# 13-Power-P3V3.net
KiCad netlist of a schematic drawn in Altium Designer
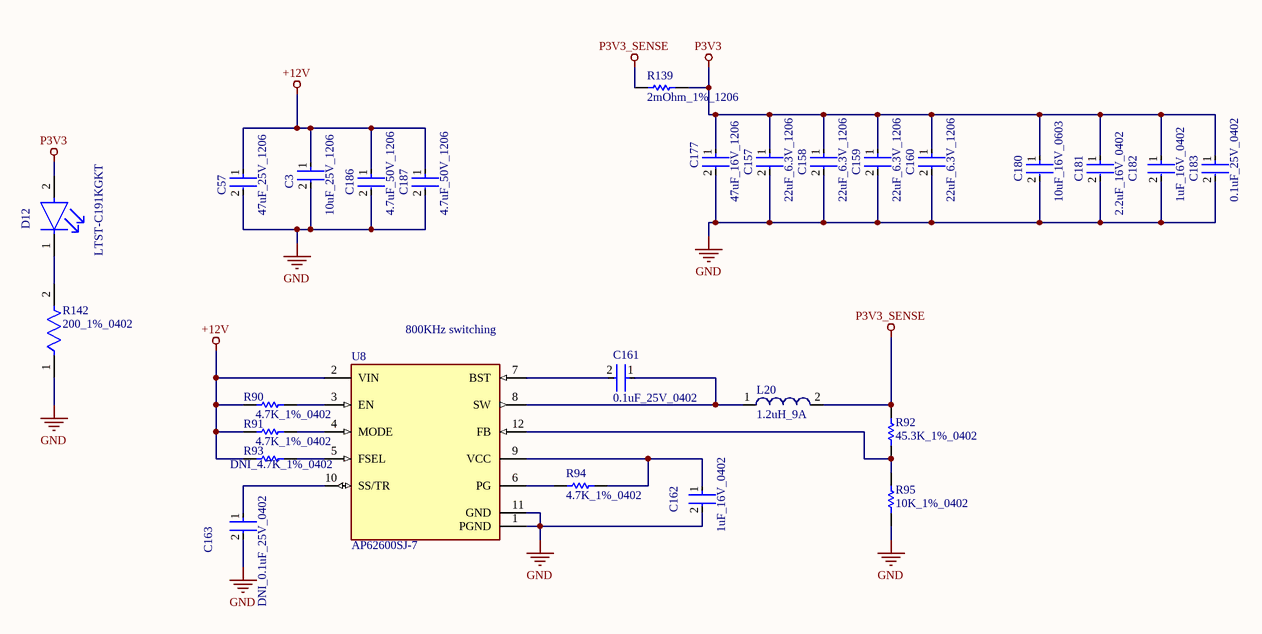
[diagram p0: 13-Power-P3V3.SchDoc]

(export (version "E")
  (design (tool "Eeschema 10.0.6"))
  (components
    (comp (ref "C3")
      (value "10uF_25V_1206")
      (footprint "FP-1206-L_3_2_0_2-W_1_6_0-IPC_A")
      (description "General Purpose Ceramic Capacitor, 1206, 10uF, 20%, X5R, 15%, 25V")
      (fields (field (name "TOLERANCE") "20%"))
      (libsource (lib "Altium Content Vault") (part "02cd4be3c70576c341d710602a673aa"))
    )
    (comp (ref "C57")
      (value "47uF_25V_1206")
      (footprint "FP-C3216-160-0_2-MFG")
      (description "Multilayer Ceramic Capacitors 47uF ±20% 25V X5R SMD 1206")
      (fields (field (name "VOLTAGE") "25V") (field (name "TOLERANCE") "20%"))
      (libsource (lib "Altium Content Vault") (part "11868f565c42a9108669ba33697ecf6"))
    )
    (comp (ref "C157")
      (value "22uF_6.3V_1206")
      (footprint "FP-1206-L_3_2_0_2-W_1_6_0-IPC_C")
      (description "General Purpose Ceramic Capacitor, 1206, 22uF, 20%, X5R, 15%, 6.3V")
      (fields (field (name "TOLERANCE") "20%") (field (name "VOLTAGE") "6.3V"))
      (libsource (lib "Altium Content Vault") (part "02cd4be3c70576c341d710602a673aa"))
    )
    (comp (ref "C158")
      (value "22uF_6.3V_1206")
      (footprint "FP-1206-L_3_2_0_2-W_1_6_0-IPC_C")
      (description "General Purpose Ceramic Capacitor, 1206, 22uF, 20%, X5R, 15%, 6.3V")
      (fields (field (name "TOLERANCE") "20%") (field (name "VOLTAGE") "6.3V"))
      (libsource (lib "Altium Content Vault") (part "02cd4be3c70576c341d710602a673aa"))
    )
    (comp (ref "C159")
      (value "22uF_6.3V_1206")
      (footprint "FP-1206-L_3_2_0_2-W_1_6_0-IPC_C")
      (description "General Purpose Ceramic Capacitor, 1206, 22uF, 20%, X5R, 15%, 6.3V")
      (fields (field (name "TOLERANCE") "20%") (field (name "VOLTAGE") "6.3V"))
      (libsource (lib "Altium Content Vault") (part "02cd4be3c70576c341d710602a673aa"))
    )
    (comp (ref "C160")
      (value "22uF_6.3V_1206")
      (footprint "FP-1206-L_3_2_0_2-W_1_6_0-IPC_C")
      (description "General Purpose Ceramic Capacitor, 1206, 22uF, 20%, X5R, 15%, 6.3V")
      (fields (field (name "TOLERANCE") "20%") (field (name "VOLTAGE") "6.3V"))
      (libsource (lib "Altium Content Vault") (part "02cd4be3c70576c341d710602a673aa"))
    )
    (comp (ref "C161")
      (value "0.1uF_25V_0402")
      (footprint "FP-0402-L_1_0_1-W_0_5_0_1-IPC_C")
      (description "General Purpose Ceramic Capacitor, 0402, 100nF, 10%, X7R, 15%, 25V")
      (fields (field (name "VOLTAGE") "25V") (field (name "TOLERANCE") "10%"))
      (libsource (lib "Altium Content Vault") (part "b4654b650e69147ec39a6b967a45e02"))
    )
    (comp (ref "C162")
      (value "1uF_16V_0402")
      (footprint "FP-0402-L_1_0_0_05-W_0_5-IPC_A")
      (description "None")
      (fields (field (name "TOLERANCE") "10%"))
      (libsource (lib "Altium Content Vault") (part "b4654b650e69147ec39a6b967a45e02"))
    )
    (comp (ref "C163")
      (value "DNI_0.1uF_25V_0402")
      (footprint "FP-0402-L_1_0_1-W_0_5_0_1-IPC_C")
      (description "General Purpose Ceramic Capacitor, 0402, 100nF, 10%, X7R, 15%, 25V")
      (fields (field (name "VOLTAGE") "25V") (field (name "TOLERANCE") "10%"))
      (libsource (lib "Altium Content Vault") (part "b4654b650e69147ec39a6b967a45e02"))
    )
    (comp (ref "C177")
      (value "47uF_16V_1206")
      (footprint "FP-C3216-160-0_2-MFG")
      (description "Multilayer Ceramic Capacitors 47uF ±20% 16V X5R SMD 1206")
      (fields (field (name "TOLERANCE") "20%"))
      (libsource (lib "Altium Content Vault") (part "11868f565c42a9108669ba33697ecf6"))
    )
    (comp (ref "C180")
      (value "10uF_16V_0603")
      (footprint "FP-0603-L_1_6_0_2-W_0_8_0-MFG")
      (description "Multilayer Ceramic Capacitor 10uF 16V X5R 20% SMD 0603 T/R")
      (fields (field (name "TOLERANCE") "20%"))
      (libsource (lib "Altium Content Vault") (part "b4654b650e69147ec39a6b967a45e02"))
    )
    (comp (ref "C181")
      (value "2.2uF_16V_0402")
      (footprint "FP-C1005-050-0_05-IPC_A")
      (description "Multilayer Ceramic Capacitors 2.2μF ±10% 16V X5R SMD 0402")
      (fields (field (name "TOLERANCE") "10%"))
      (libsource (lib "Altium Content Vault") (part "b4654b650e69147ec39a6b967a45e02"))
    )
    (comp (ref "C182")
      (value "1uF_16V_0402")
      (footprint "FP-0402-L_1_0_0_05-W_0_5-IPC_A")
      (description "None")
      (fields (field (name "TOLERANCE") "10%"))
      (libsource (lib "Altium Content Vault") (part "b4654b650e69147ec39a6b967a45e02"))
    )
    (comp (ref "C183")
      (value "0.1uF_25V_0402")
      (footprint "FP-0402-L_1_0_1-W_0_5_0_1-IPC_C")
      (description "General Purpose Ceramic Capacitor, 0402, 100nF, 10%, X7R, 15%, 25V")
      (fields (field (name "VOLTAGE") "25V") (field (name "TOLERANCE") "10%"))
      (libsource (lib "Altium Content Vault") (part "b4654b650e69147ec39a6b967a45e02"))
    )
    (comp (ref "C186")
      (value "4.7uF_50V_1206")
      (footprint "FP-GRM31C-0_2-e0_3_0_8-IPC_C")
      (description "Chip Multilayer Ceramic Capacitors for General Purpose, 1206, 4.7uF, X7R, 15%, 10%, 50V")
      (fields (field (name "VOLTAGE") "50V") (field (name "TOLERANCE") "10%"))
      (libsource (lib "Altium Content Vault") (part "02cd4be3c70576c341d710602a673aa"))
    )
    (comp (ref "C187")
      (value "4.7uF_50V_1206")
      (footprint "FP-GRM31C-0_2-e0_3_0_8-IPC_C")
      (description "Chip Multilayer Ceramic Capacitors for General Purpose, 1206, 4.7uF, X7R, 15%, 10%, 50V")
      (fields (field (name "VOLTAGE") "50V") (field (name "TOLERANCE") "10%"))
      (libsource (lib "Altium Content Vault") (part "02cd4be3c70576c341d710602a673aa"))
    )
    (comp (ref "D12")
      (value "LTST-C191KGKT")
      (footprint "FP-LTST-C191KGKT-MFG")
      (description "LED GREEN CLEAR SMD")
      (libsource (lib "Altium Content Vault") (part "8706943c75ba83719d021d2fdc84c58"))
    )
    (comp (ref "L20")
      (value "1.2uH_9A")
      (footprint "WE-LHMI 7050")
      (description "SMD Power Inductor WE-LHMI, L=1.2 µH")
      (fields (field (name "MANUFACTURER") "Wuerth Elektronik") (field (name "PARTNUMBER") "74437349012"))
      (libsource (lib "Altium Content Vault") (part "WE-IND-INDUCTOR-2"))
    )
    (comp (ref "R90")
      (value "4.7K_1%_0402")
      (footprint "RESC1005X40X25NL10T10")
      (fields (field (name "MANUFACTURER") "Bourns") (field (name "PART NUMBER") "CR0402-FX-4701GLF"))
      (libsource (lib "Altium Content Vault") (part "RES"))
    )
    (comp (ref "R91")
      (value "4.7K_1%_0402")
      (footprint "RESC1005X40X25NL10T10")
      (fields (field (name "MANUFACTURER") "Bourns") (field (name "PART NUMBER") "CR0402-FX-4701GLF"))
      (libsource (lib "Altium Content Vault") (part "RES"))
    )
    (comp (ref "R92")
      (value "45.3K_1%_0402")
      (footprint "RESC1005X40X25ML05T10")
      (fields (field (name "PART NUMBER") "RC0402FR-0745K3L") (field (name "MANUFACTURER") "Yageo / Phycomp"))
      (libsource (lib "Altium Content Vault") (part "RES"))
    )
    (comp (ref "R93")
      (value "DNI_4.7K_1%_0402")
      (footprint "RESC1005X40X25NL10T10")
      (fields (field (name "MANUFACTURER") "Bourns") (field (name "PART NUMBER") "CR0402-FX-4701GLF"))
      (libsource (lib "Altium Content Vault") (part "RES"))
    )
    (comp (ref "R94")
      (value "4.7K_1%_0402")
      (footprint "RESC1005X40X25NL10T10")
      (fields (field (name "MANUFACTURER") "Bourns") (field (name "PART NUMBER") "CR0402-FX-4701GLF"))
      (libsource (lib "Altium Content Vault") (part "RES"))
    )
    (comp (ref "R95")
      (value "10K_1%_0402")
      (footprint "RESC1005X40X25NL10T10")
      (fields (field (name "MANUFACTURER") "Bourns") (field (name "PART NUMBER") "CR0402-FX-1002GLF"))
      (libsource (lib "Altium Content Vault") (part "RES"))
    )
    (comp (ref "R139")
      (value "2mOhm_1%_1206")
      (footprint "RESC3216X89X64NL25T25")
      (fields (field (name "MANUFACTURER") "Vishay Dale") (field (name "PART NUMBER") "WSL12062L000FEA18"))
      (libsource (lib "Altium Content Vault") (part "RES"))
    )
    (comp (ref "R142")
      (value "200_1%_0402")
      (footprint "FP-ERJ2RK-IPC_A")
      (description "RES SMD 200 OHM 1% 1/10W 0402")
      (fields (field (name "TOLERANCE") "1%"))
      (libsource (lib "Altium Content Vault") (part "1029c3af85768c4190bb7ad29bc67b5"))
    )
    (comp (ref "U8")
      (value "AP62600SJ-7")
      (footprint "FP-V-QFN2030-12_Type_A-MFG")
      (description "DCDC CONV HV BUCK,V-QFN2030-12")
      (libsource (lib "Altium Content Vault") (part "03c86ce2703f4b33b3045e94f7be521"))
    )
  )
  (nets
    (net (code "1") (name "+12V") (class "Default")
      (node (ref "C186") (pin "1") (pinfunction "1_1") (pintype "passive"))
      (node (ref "C187") (pin "1") (pinfunction "1_1") (pintype "passive"))
      (node (ref "C3") (pin "1") (pinfunction "1_1") (pintype "passive"))
      (node (ref "C57") (pin "1") (pinfunction "1_1") (pintype "passive"))
      (node (ref "R90") (pin "1") (pinfunction "1_1") (pintype "passive"))
      (node (ref "R91") (pin "1") (pinfunction "1_1") (pintype "passive"))
      (node (ref "R93") (pin "1") (pinfunction "1_1") (pintype "passive"))
      (node (ref "U8") (pin "2") (pinfunction "VIN_2") (pintype "power_in"))
    )
    (net (code "2") (name "GND") (class "Default")
      (node (ref "C157") (pin "2") (pinfunction "2_2") (pintype "passive"))
      (node (ref "C158") (pin "2") (pinfunction "2_2") (pintype "passive"))
      (node (ref "C159") (pin "2") (pinfunction "2_2") (pintype "passive"))
      (node (ref "C160") (pin "2") (pinfunction "2_2") (pintype "passive"))
      (node (ref "C162") (pin "2") (pinfunction "2_2") (pintype "passive"))
      (node (ref "C163") (pin "2") (pinfunction "2_2") (pintype "passive"))
      (node (ref "C177") (pin "2") (pinfunction "2_2") (pintype "passive"))
      (node (ref "C180") (pin "2") (pinfunction "2_2") (pintype "passive"))
      (node (ref "C181") (pin "2") (pinfunction "2_2") (pintype "passive"))
      (node (ref "C182") (pin "2") (pinfunction "2_2") (pintype "passive"))
      (node (ref "C183") (pin "2") (pinfunction "2_2") (pintype "passive"))
      (node (ref "C186") (pin "2") (pinfunction "2_2") (pintype "passive"))
      (node (ref "C187") (pin "2") (pinfunction "2_2") (pintype "passive"))
      (node (ref "C3") (pin "2") (pinfunction "2_2") (pintype "passive"))
      (node (ref "C57") (pin "2") (pinfunction "2_2") (pintype "passive"))
      (node (ref "R142") (pin "1") (pinfunction "1_1") (pintype "passive"))
      (node (ref "R95") (pin "1") (pinfunction "1_1") (pintype "passive"))
      (node (ref "U8") (pin "1") (pinfunction "PGND_1") (pintype "power_in"))
      (node (ref "U8") (pin "11") (pinfunction "GND_11") (pintype "power_in"))
    )
    (net (code "3") (name "Net-(D12-C)") (class "Default")
      (node (ref "D12") (pin "1") (pinfunction "C_1") (pintype "passive"))
      (node (ref "R142") (pin "2") (pinfunction "2_2") (pintype "passive"))
    )
    (net (code "4") (name "Net-(U8-BST)") (class "Default")
      (node (ref "C161") (pin "2") (pinfunction "2_2") (pintype "passive"))
      (node (ref "U8") (pin "7") (pinfunction "BST_7") (pintype "input"))
    )
    (net (code "5") (name "Net-(U8-EN)") (class "Default")
      (node (ref "R90") (pin "2") (pinfunction "2_2") (pintype "passive"))
      (node (ref "U8") (pin "3") (pinfunction "EN_3") (pintype "input"))
    )
    (net (code "6") (name "Net-(U8-FB)") (class "Default")
      (node (ref "R92") (pin "1") (pinfunction "1_1") (pintype "passive"))
      (node (ref "R95") (pin "2") (pinfunction "2_2") (pintype "passive"))
      (node (ref "U8") (pin "12") (pinfunction "FB_12") (pintype "input"))
    )
    (net (code "7") (name "Net-(U8-FSEL)") (class "Default")
      (node (ref "R93") (pin "2") (pinfunction "2_2") (pintype "passive"))
      (node (ref "U8") (pin "5") (pinfunction "FSEL_5") (pintype "input"))
    )
    (net (code "8") (name "Net-(U8-MODE)") (class "Default")
      (node (ref "R91") (pin "2") (pinfunction "2_2") (pintype "passive"))
      (node (ref "U8") (pin "4") (pinfunction "MODE_4") (pintype "input"))
    )
    (net (code "9") (name "Net-(U8-PG)") (class "Default")
      (node (ref "R94") (pin "2") (pinfunction "2_2") (pintype "passive"))
      (node (ref "U8") (pin "6") (pinfunction "PG_6") (pintype "open_collector"))
    )
    (net (code "10") (name "Net-(U8-SS{slash}TR)") (class "Default")
      (node (ref "C163") (pin "1") (pinfunction "1_1") (pintype "passive"))
      (node (ref "U8") (pin "10") (pinfunction "SS/TR_10") (pintype "bidirectional"))
    )
    (net (code "11") (name "Net-(U8-SW)") (class "Default")
      (node (ref "C161") (pin "1") (pinfunction "1_1") (pintype "passive"))
      (node (ref "L20") (pin "1") (pinfunction "1_1") (pintype "passive"))
      (node (ref "U8") (pin "8") (pinfunction "SW_8") (pintype "output"))
    )
    (net (code "12") (name "Net-(U8-VCC)") (class "Default")
      (node (ref "C162") (pin "1") (pinfunction "1_1") (pintype "passive"))
      (node (ref "R94") (pin "1") (pinfunction "1_1") (pintype "passive"))
      (node (ref "U8") (pin "9") (pinfunction "VCC_9") (pintype "power_in"))
    )
    (net (code "13") (name "P3V3") (class "Default")
      (node (ref "C157") (pin "1") (pinfunction "1_1") (pintype "passive"))
      (node (ref "C158") (pin "1") (pinfunction "1_1") (pintype "passive"))
      (node (ref "C159") (pin "1") (pinfunction "1_1") (pintype "passive"))
      (node (ref "C160") (pin "1") (pinfunction "1_1") (pintype "passive"))
      (node (ref "C177") (pin "1") (pinfunction "1_1") (pintype "passive"))
      (node (ref "C180") (pin "1") (pinfunction "1_1") (pintype "passive"))
      (node (ref "C181") (pin "1") (pinfunction "1_1") (pintype "passive"))
      (node (ref "C182") (pin "1") (pinfunction "1_1") (pintype "passive"))
      (node (ref "C183") (pin "1") (pinfunction "1_1") (pintype "passive"))
      (node (ref "D12") (pin "2") (pinfunction "A_2") (pintype "passive"))
      (node (ref "R139") (pin "2") (pinfunction "2_2") (pintype "passive"))
    )
    (net (code "14") (name "P3V3_SENSE") (class "Default")
      (node (ref "L20") (pin "2") (pinfunction "2_2") (pintype "passive"))
      (node (ref "R139") (pin "1") (pinfunction "1_1") (pintype "passive"))
      (node (ref "R92") (pin "2") (pinfunction "2_2") (pintype "passive"))
    )
  )
)
